# arduinoCurrentSensor.net
KiCad netlist of a schematic drawn in EAGLE
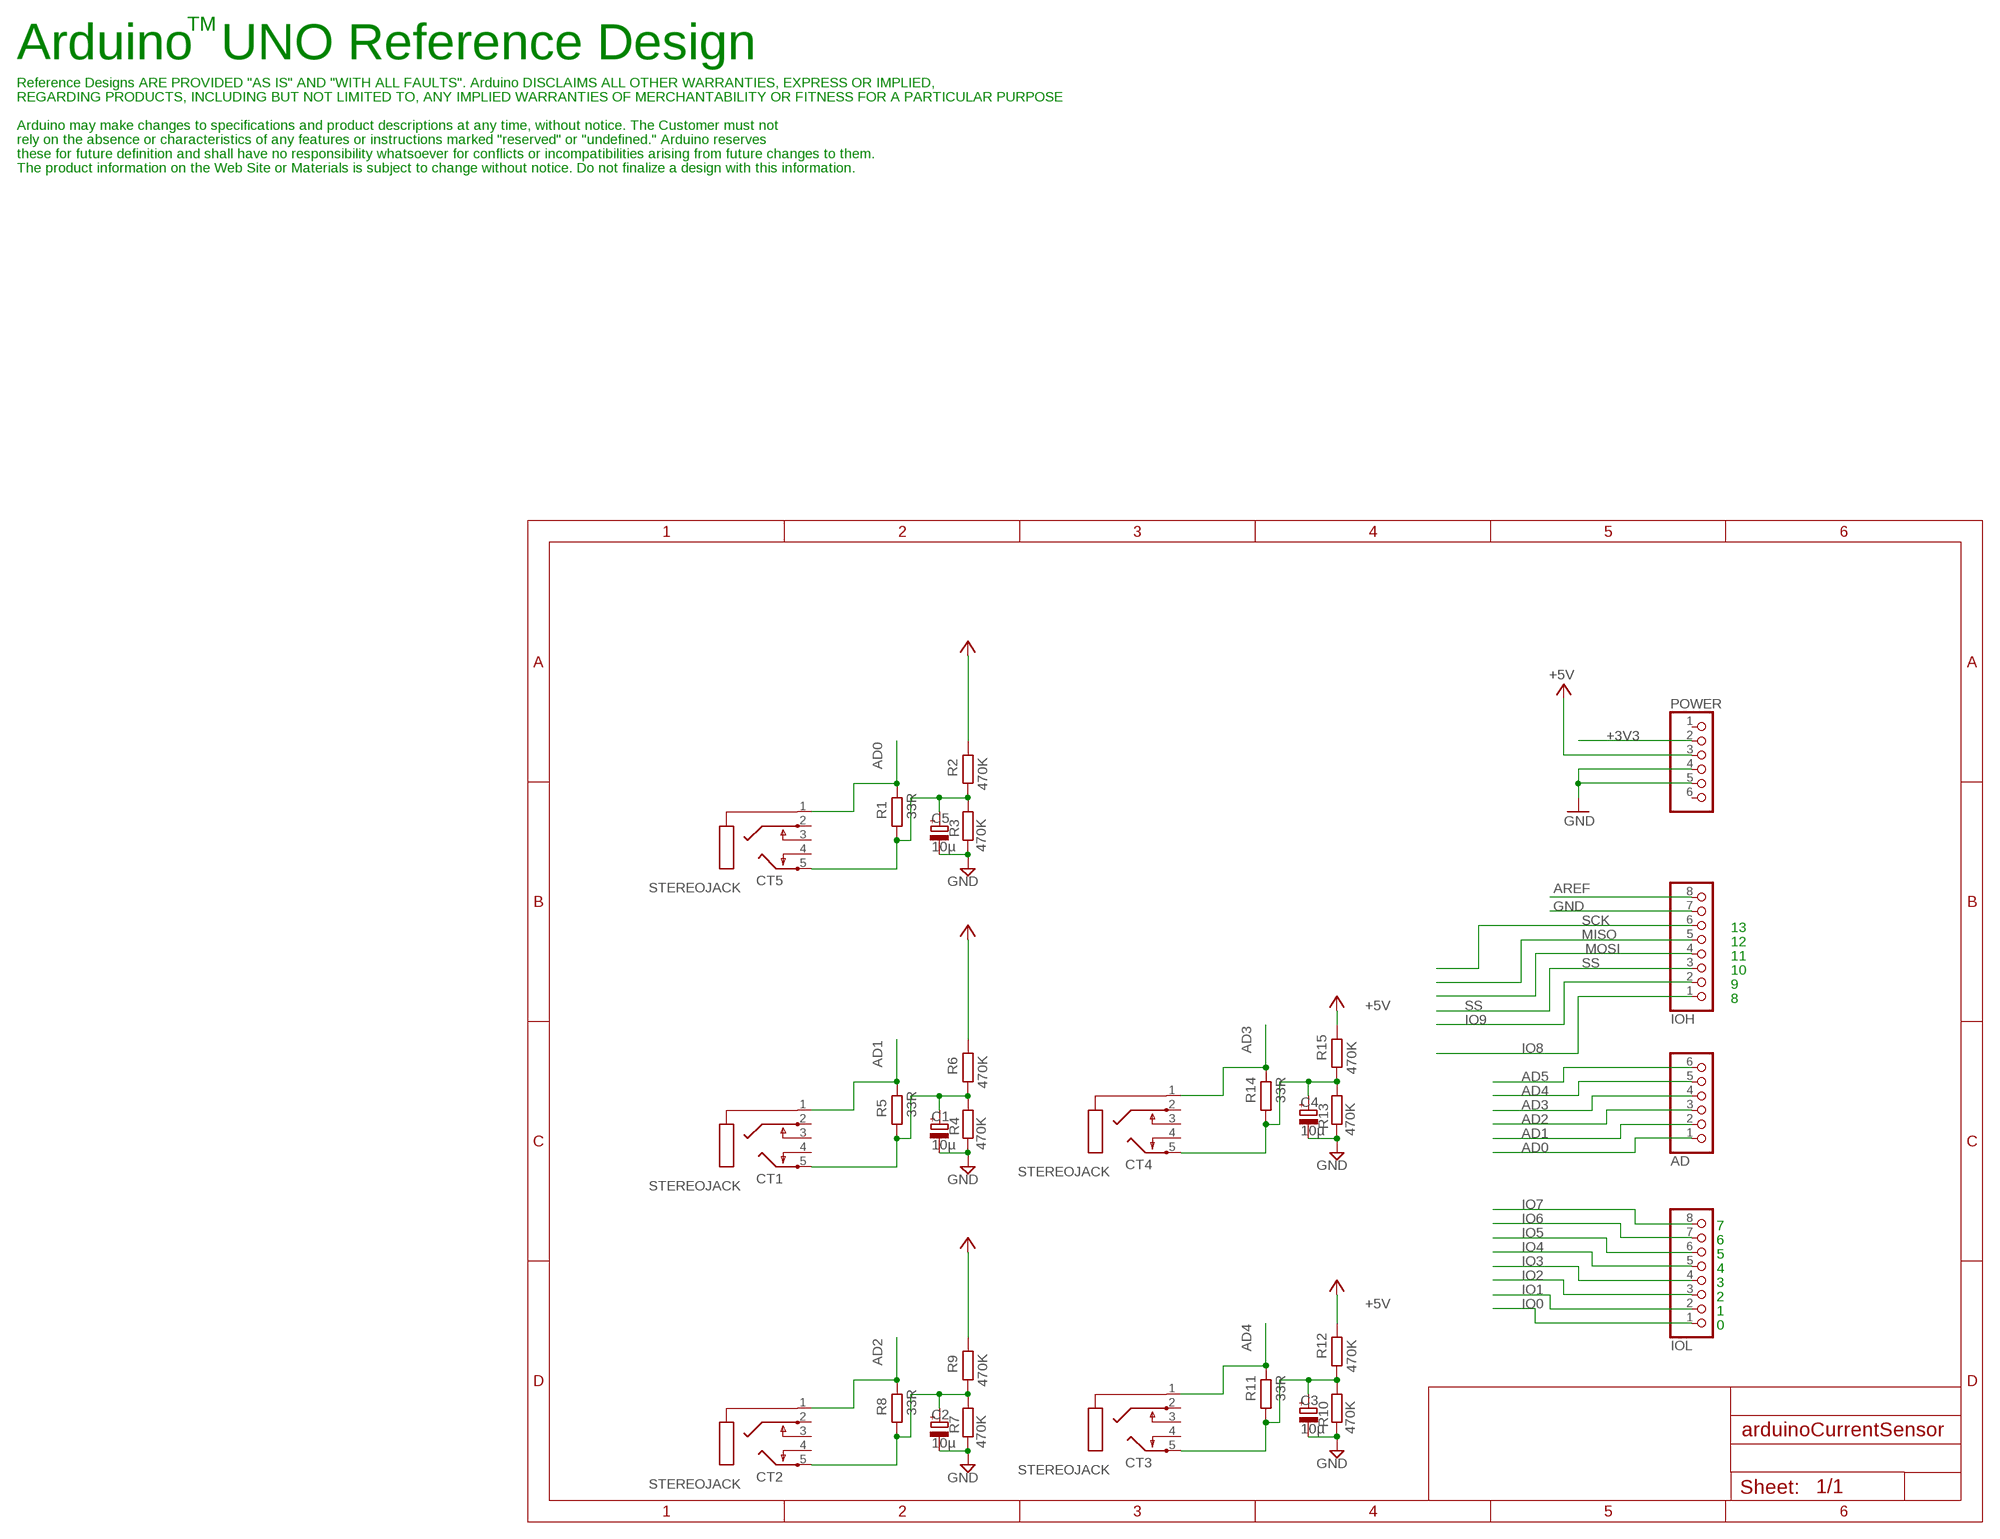
[diagram p0: schematic, sheet 1]

(export (version "E")
  (design (tool "Eeschema 10.0.6"))
  (components
    (comp (ref "AD")
      (value "PINHD-1X6")
      (footprint "eagle-import:1X06")
      (libsource (lib "eagle-import") (part "PINHD-1X6"))
    )
    (comp (ref "C1")
      (value "10µ")
      (footprint "eagle-import:E2-5")
      (libsource (lib "eagle-import") (part "CPOL-EUE2-5"))
    )
    (comp (ref "C2")
      (value "10µ")
      (footprint "eagle-import:E2-5")
      (libsource (lib "eagle-import") (part "CPOL-EUE2-5"))
    )
    (comp (ref "C3")
      (value "10µ")
      (footprint "eagle-import:E2-5")
      (libsource (lib "eagle-import") (part "CPOL-EUE2-5"))
    )
    (comp (ref "C4")
      (value "10µ")
      (footprint "eagle-import:E2-5")
      (libsource (lib "eagle-import") (part "CPOL-EUE2-5"))
    )
    (comp (ref "C5")
      (value "10µ")
      (footprint "eagle-import:E2-5")
      (libsource (lib "eagle-import") (part "CPOL-EUE2-5"))
    )
    (comp (ref "CT1")
      (value "STEREOJACK")
      (footprint "eagle-import:STX3100")
      (libsource (lib "eagle-import") (part "STEREOJACK"))
    )
    (comp (ref "CT2")
      (value "STEREOJACK")
      (footprint "eagle-import:STX3100")
      (libsource (lib "eagle-import") (part "STEREOJACK"))
    )
    (comp (ref "CT3")
      (value "STEREOJACK")
      (footprint "eagle-import:STX3100")
      (libsource (lib "eagle-import") (part "STEREOJACK"))
    )
    (comp (ref "CT4")
      (value "STEREOJACK")
      (footprint "eagle-import:STX3100")
      (libsource (lib "eagle-import") (part "STEREOJACK"))
    )
    (comp (ref "CT5")
      (value "STEREOJACK")
      (footprint "eagle-import:STX3100")
      (libsource (lib "eagle-import") (part "STEREOJACK"))
    )
    (comp (ref "IOH")
      (value "PINHD-1X8")
      (footprint "eagle-import:1X08")
      (libsource (lib "eagle-import") (part "PINHD-1X8"))
    )
    (comp (ref "IOL")
      (value "PINHD-1X8")
      (footprint "eagle-import:1X08")
      (libsource (lib "eagle-import") (part "PINHD-1X8"))
    )
    (comp (ref "POWER")
      (value "PINHD-1X6")
      (footprint "eagle-import:1X06")
      (libsource (lib "eagle-import") (part "PINHD-1X6"))
    )
    (comp (ref "R1")
      (value "33R")
      (footprint "eagle-import:0204_7")
      (libsource (lib "eagle-import") (part "R-EU_0204/7"))
    )
    (comp (ref "R2")
      (value "470K")
      (footprint "eagle-import:0204_7")
      (libsource (lib "eagle-import") (part "R-EU_0204/7"))
    )
    (comp (ref "R3")
      (value "470K")
      (footprint "eagle-import:0204_7")
      (libsource (lib "eagle-import") (part "R-EU_0204/7"))
    )
    (comp (ref "R4")
      (value "470K")
      (footprint "eagle-import:0204_7")
      (libsource (lib "eagle-import") (part "R-EU_0204/7"))
    )
    (comp (ref "R5")
      (value "33R")
      (footprint "eagle-import:0204_7")
      (libsource (lib "eagle-import") (part "R-EU_0204/7"))
    )
    (comp (ref "R6")
      (value "470K")
      (footprint "eagle-import:0204_7")
      (libsource (lib "eagle-import") (part "R-EU_0204/7"))
    )
    (comp (ref "R7")
      (value "470K")
      (footprint "eagle-import:0204_7")
      (libsource (lib "eagle-import") (part "R-EU_0204/7"))
    )
    (comp (ref "R8")
      (value "33R")
      (footprint "eagle-import:0204_7")
      (libsource (lib "eagle-import") (part "R-EU_0204/7"))
    )
    (comp (ref "R9")
      (value "470K")
      (footprint "eagle-import:0204_7")
      (libsource (lib "eagle-import") (part "R-EU_0204/7"))
    )
    (comp (ref "R10")
      (value "470K")
      (footprint "eagle-import:0204_7")
      (libsource (lib "eagle-import") (part "R-EU_0204/7"))
    )
    (comp (ref "R11")
      (value "33R")
      (footprint "eagle-import:0204_7")
      (libsource (lib "eagle-import") (part "R-EU_0204/7"))
    )
    (comp (ref "R12")
      (value "470K")
      (footprint "eagle-import:0204_7")
      (libsource (lib "eagle-import") (part "R-EU_0204/7"))
    )
    (comp (ref "R13")
      (value "470K")
      (footprint "eagle-import:0204_7")
      (libsource (lib "eagle-import") (part "R-EU_0204/7"))
    )
    (comp (ref "R14")
      (value "33R")
      (footprint "eagle-import:0204_7")
      (libsource (lib "eagle-import") (part "R-EU_0204/7"))
    )
    (comp (ref "R15")
      (value "470K")
      (footprint "eagle-import:0204_7")
      (libsource (lib "eagle-import") (part "R-EU_0204/7"))
    )
  )
  (nets
    (net (code "1") (name "+5V") (class "Default")
      (node (ref "POWER") (pin "3") (pinfunction "3_3") (pintype "passive"))
      (node (ref "R12") (pin "2") (pinfunction "2_2") (pintype "passive"))
      (node (ref "R15") (pin "2") (pinfunction "2_2") (pintype "passive"))
      (node (ref "R2") (pin "2") (pinfunction "2_2") (pintype "passive"))
      (node (ref "R6") (pin "2") (pinfunction "2_2") (pintype "passive"))
      (node (ref "R9") (pin "2") (pinfunction "2_2") (pintype "passive"))
    )
    (net (code "2") (name "/+3V3") (class "Default")
      (node (ref "POWER") (pin "2") (pinfunction "2_2") (pintype "passive"))
    )
    (net (code "3") (name "/AD0") (class "Default")
      (node (ref "AD") (pin "1") (pinfunction "1_1") (pintype "passive"))
      (node (ref "CT5") (pin "1") (pinfunction "1_1") (pintype "passive"))
      (node (ref "R1") (pin "2") (pinfunction "2_2") (pintype "passive"))
    )
    (net (code "4") (name "/AD1") (class "Default")
      (node (ref "AD") (pin "2") (pinfunction "2_2") (pintype "passive"))
      (node (ref "CT1") (pin "1") (pinfunction "1_1") (pintype "passive"))
      (node (ref "R5") (pin "2") (pinfunction "2_2") (pintype "passive"))
    )
    (net (code "5") (name "/AD2") (class "Default")
      (node (ref "AD") (pin "3") (pinfunction "3_3") (pintype "passive"))
      (node (ref "CT2") (pin "1") (pinfunction "1_1") (pintype "passive"))
      (node (ref "R8") (pin "2") (pinfunction "2_2") (pintype "passive"))
    )
    (net (code "6") (name "/AD3") (class "Default")
      (node (ref "AD") (pin "4") (pinfunction "4_4") (pintype "passive"))
      (node (ref "CT4") (pin "1") (pinfunction "1_1") (pintype "passive"))
      (node (ref "R14") (pin "2") (pinfunction "2_2") (pintype "passive"))
    )
    (net (code "7") (name "/AD4") (class "Default")
      (node (ref "AD") (pin "5") (pinfunction "5_5") (pintype "passive"))
      (node (ref "CT3") (pin "1") (pinfunction "1_1") (pintype "passive"))
      (node (ref "R11") (pin "2") (pinfunction "2_2") (pintype "passive"))
    )
    (net (code "8") (name "/AD5") (class "Default")
      (node (ref "AD") (pin "6") (pinfunction "6_6") (pintype "passive"))
    )
    (net (code "9") (name "/AREF") (class "Default")
      (node (ref "IOH") (pin "8") (pinfunction "8_8") (pintype "passive"))
    )
    (net (code "10") (name "/IO0") (class "Default")
      (node (ref "IOL") (pin "1") (pinfunction "1_1") (pintype "passive"))
    )
    (net (code "11") (name "/IO1") (class "Default")
      (node (ref "IOL") (pin "2") (pinfunction "2_2") (pintype "passive"))
    )
    (net (code "12") (name "/IO2") (class "Default")
      (node (ref "IOL") (pin "3") (pinfunction "3_3") (pintype "passive"))
    )
    (net (code "13") (name "/IO3") (class "Default")
      (node (ref "IOL") (pin "4") (pinfunction "4_4") (pintype "passive"))
    )
    (net (code "14") (name "/IO4") (class "Default")
      (node (ref "IOL") (pin "5") (pinfunction "5_5") (pintype "passive"))
    )
    (net (code "15") (name "/IO5") (class "Default")
      (node (ref "IOL") (pin "6") (pinfunction "6_6") (pintype "passive"))
    )
    (net (code "16") (name "/IO6") (class "Default")
      (node (ref "IOL") (pin "7") (pinfunction "7_7") (pintype "passive"))
    )
    (net (code "17") (name "/IO7") (class "Default")
      (node (ref "IOL") (pin "8") (pinfunction "8_8") (pintype "passive"))
    )
    (net (code "18") (name "/IO8") (class "Default")
      (node (ref "IOH") (pin "1") (pinfunction "1_1") (pintype "passive"))
    )
    (net (code "19") (name "/IO9") (class "Default")
      (node (ref "IOH") (pin "2") (pinfunction "2_2") (pintype "passive"))
    )
    (net (code "20") (name "/MISO") (class "Default")
      (node (ref "IOH") (pin "5") (pinfunction "5_5") (pintype "passive"))
    )
    (net (code "21") (name "/MOSI") (class "Default")
      (node (ref "IOH") (pin "4") (pinfunction "4_4") (pintype "passive"))
    )
    (net (code "22") (name "/SCK") (class "Default")
      (node (ref "IOH") (pin "6") (pinfunction "6_6") (pintype "passive"))
    )
    (net (code "23") (name "/SS") (class "Default")
      (node (ref "IOH") (pin "3") (pinfunction "3_3") (pintype "passive"))
    )
    (net (code "24") (name "GND") (class "Default")
      (node (ref "C1") (pin "-") (pinfunction "-_-") (pintype "passive"))
      (node (ref "C2") (pin "-") (pinfunction "-_-") (pintype "passive"))
      (node (ref "C3") (pin "-") (pinfunction "-_-") (pintype "passive"))
      (node (ref "C4") (pin "-") (pinfunction "-_-") (pintype "passive"))
      (node (ref "C5") (pin "-") (pinfunction "-_-") (pintype "passive"))
      (node (ref "IOH") (pin "7") (pinfunction "7_7") (pintype "passive"))
      (node (ref "POWER") (pin "4") (pinfunction "4_4") (pintype "passive"))
      (node (ref "POWER") (pin "5") (pinfunction "5_5") (pintype "passive"))
      (node (ref "R10") (pin "2") (pinfunction "2_2") (pintype "passive"))
      (node (ref "R13") (pin "2") (pinfunction "2_2") (pintype "passive"))
      (node (ref "R3") (pin "2") (pinfunction "2_2") (pintype "passive"))
      (node (ref "R4") (pin "2") (pinfunction "2_2") (pintype "passive"))
      (node (ref "R7") (pin "2") (pinfunction "2_2") (pintype "passive"))
    )
    (net (code "25") (name "Net-(C1-Pad+)") (class "Default")
      (node (ref "C1") (pin "+") (pinfunction "+_+") (pintype "passive"))
      (node (ref "CT1") (pin "5") (pinfunction "5_5") (pintype "passive"))
      (node (ref "R4") (pin "1") (pinfunction "1_1") (pintype "passive"))
      (node (ref "R5") (pin "1") (pinfunction "1_1") (pintype "passive"))
      (node (ref "R6") (pin "1") (pinfunction "1_1") (pintype "passive"))
    )
    (net (code "26") (name "Net-(C2-Pad+)") (class "Default")
      (node (ref "C2") (pin "+") (pinfunction "+_+") (pintype "passive"))
      (node (ref "CT2") (pin "5") (pinfunction "5_5") (pintype "passive"))
      (node (ref "R7") (pin "1") (pinfunction "1_1") (pintype "passive"))
      (node (ref "R8") (pin "1") (pinfunction "1_1") (pintype "passive"))
      (node (ref "R9") (pin "1") (pinfunction "1_1") (pintype "passive"))
    )
    (net (code "27") (name "Net-(C3-Pad+)") (class "Default")
      (node (ref "C3") (pin "+") (pinfunction "+_+") (pintype "passive"))
      (node (ref "CT3") (pin "5") (pinfunction "5_5") (pintype "passive"))
      (node (ref "R10") (pin "1") (pinfunction "1_1") (pintype "passive"))
      (node (ref "R11") (pin "1") (pinfunction "1_1") (pintype "passive"))
      (node (ref "R12") (pin "1") (pinfunction "1_1") (pintype "passive"))
    )
    (net (code "28") (name "Net-(C4-Pad+)") (class "Default")
      (node (ref "C4") (pin "+") (pinfunction "+_+") (pintype "passive"))
      (node (ref "CT4") (pin "5") (pinfunction "5_5") (pintype "passive"))
      (node (ref "R13") (pin "1") (pinfunction "1_1") (pintype "passive"))
      (node (ref "R14") (pin "1") (pinfunction "1_1") (pintype "passive"))
      (node (ref "R15") (pin "1") (pinfunction "1_1") (pintype "passive"))
    )
    (net (code "29") (name "Net-(C5-Pad+)") (class "Default")
      (node (ref "C5") (pin "+") (pinfunction "+_+") (pintype "passive"))
      (node (ref "CT5") (pin "5") (pinfunction "5_5") (pintype "passive"))
      (node (ref "R1") (pin "1") (pinfunction "1_1") (pintype "passive"))
      (node (ref "R2") (pin "1") (pinfunction "1_1") (pintype "passive"))
      (node (ref "R3") (pin "1") (pinfunction "1_1") (pintype "passive"))
    )
    (net (code "30") (name "unconnected-(CT1-Pad2)") (class "Default")
      (node (ref "CT1") (pin "2") (pinfunction "2_2") (pintype "passive"))
    )
    (net (code "31") (name "unconnected-(CT1-Pad3)") (class "Default")
      (node (ref "CT1") (pin "3") (pinfunction "3_3") (pintype "passive"))
    )
    (net (code "32") (name "unconnected-(CT1-Pad4)") (class "Default")
      (node (ref "CT1") (pin "4") (pinfunction "4_4") (pintype "passive"))
    )
    (net (code "33") (name "unconnected-(CT2-Pad2)") (class "Default")
      (node (ref "CT2") (pin "2") (pinfunction "2_2") (pintype "passive"))
    )
    (net (code "34") (name "unconnected-(CT2-Pad3)") (class "Default")
      (node (ref "CT2") (pin "3") (pinfunction "3_3") (pintype "passive"))
    )
    (net (code "35") (name "unconnected-(CT2-Pad4)") (class "Default")
      (node (ref "CT2") (pin "4") (pinfunction "4_4") (pintype "passive"))
    )
    (net (code "36") (name "unconnected-(CT3-Pad2)") (class "Default")
      (node (ref "CT3") (pin "2") (pinfunction "2_2") (pintype "passive"))
    )
    (net (code "37") (name "unconnected-(CT3-Pad3)") (class "Default")
      (node (ref "CT3") (pin "3") (pinfunction "3_3") (pintype "passive"))
    )
    (net (code "38") (name "unconnected-(CT3-Pad4)") (class "Default")
      (node (ref "CT3") (pin "4") (pinfunction "4_4") (pintype "passive"))
    )
    (net (code "39") (name "unconnected-(CT4-Pad2)") (class "Default")
      (node (ref "CT4") (pin "2") (pinfunction "2_2") (pintype "passive"))
    )
    (net (code "40") (name "unconnected-(CT4-Pad3)") (class "Default")
      (node (ref "CT4") (pin "3") (pinfunction "3_3") (pintype "passive"))
    )
    (net (code "41") (name "unconnected-(CT4-Pad4)") (class "Default")
      (node (ref "CT4") (pin "4") (pinfunction "4_4") (pintype "passive"))
    )
    (net (code "42") (name "unconnected-(CT5-Pad2)") (class "Default")
      (node (ref "CT5") (pin "2") (pinfunction "2_2") (pintype "passive"))
    )
    (net (code "43") (name "unconnected-(CT5-Pad3)") (class "Default")
      (node (ref "CT5") (pin "3") (pinfunction "3_3") (pintype "passive"))
    )
    (net (code "44") (name "unconnected-(CT5-Pad4)") (class "Default")
      (node (ref "CT5") (pin "4") (pinfunction "4_4") (pintype "passive"))
    )
    (net (code "45") (name "unconnected-(POWER-Pad1)") (class "Default")
      (node (ref "POWER") (pin "1") (pinfunction "1_1") (pintype "passive"))
    )
    (net (code "46") (name "unconnected-(POWER-Pad6)") (class "Default")
      (node (ref "POWER") (pin "6") (pinfunction "6_6") (pintype "passive"))
    )
  )
)
